# DRVLED.net
KiCad netlist of a schematic drawn in Altium Designer
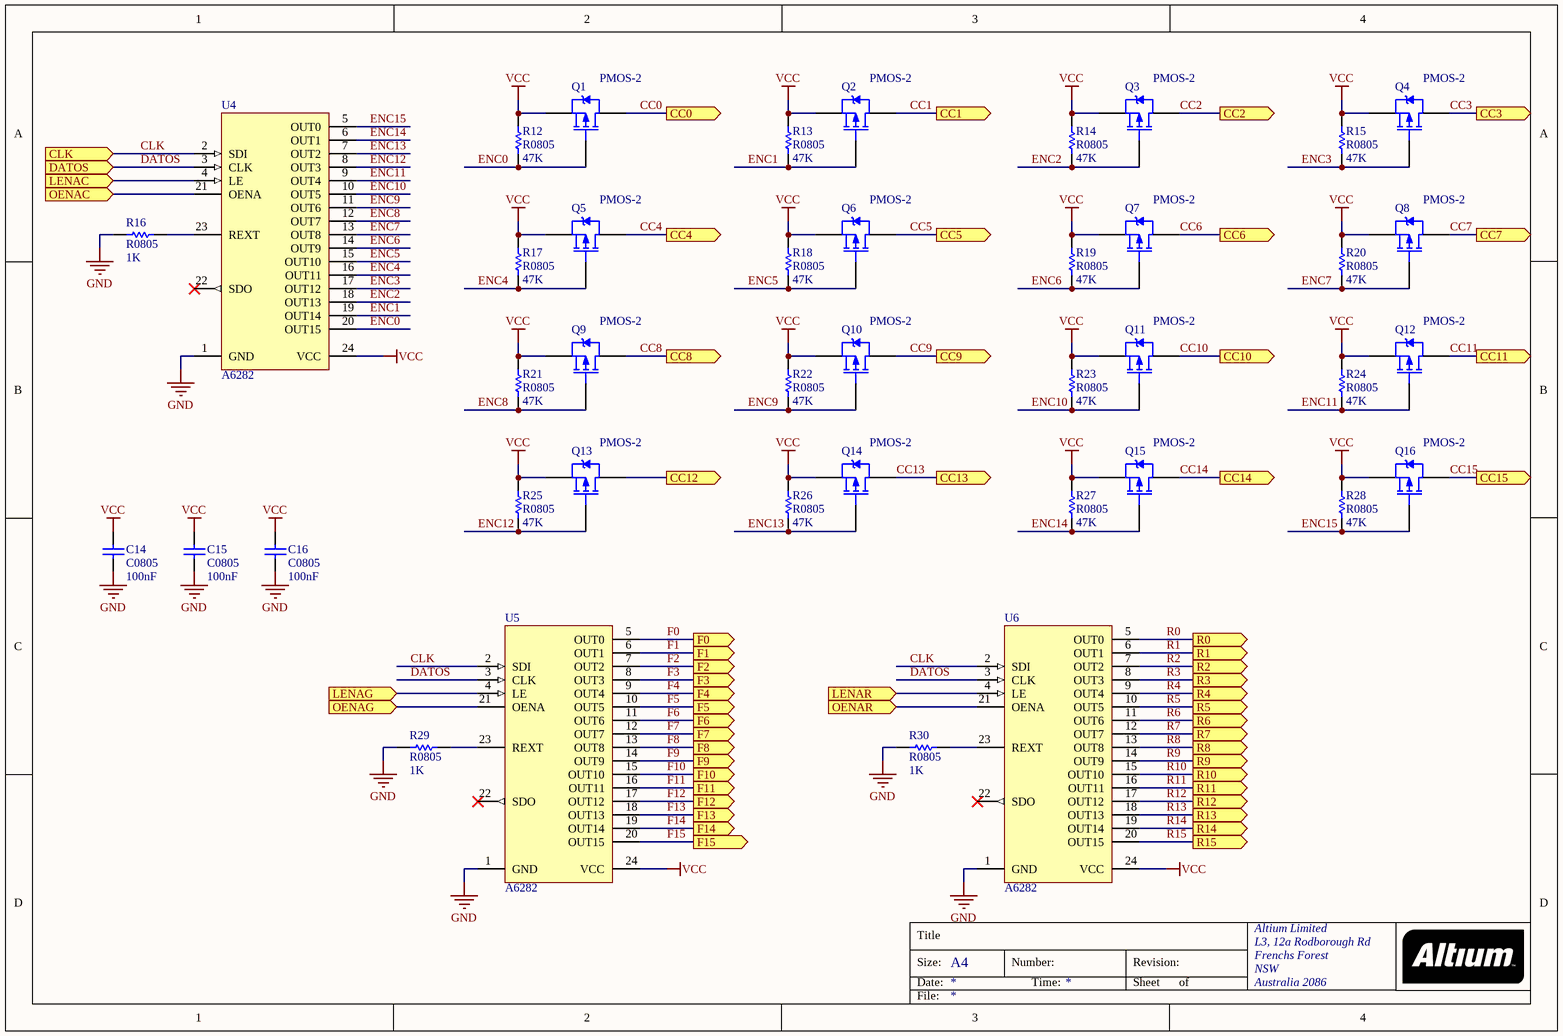
[diagram p0: DRVLED.SchDoc]

(export (version "E")
  (design (tool "Eeschema 10.0.6"))
  (components
    (comp (ref "C14")
      (value "C0805")
      (footprint "C0805C")
      (description "Cap 100nF 25V X7R")
      (fields
        (field (name "PART") "399-1170-1-ND")
        (field (name "ALTIUM_VALUE") "100nF")
        (field (name "PUBLISHER") "Altium Limited")
      )
      (libsource (lib "PROPIASchlib") (part "Cap 0805 100nF"))
    )
    (comp (ref "C15")
      (value "C0805")
      (footprint "C0805C")
      (description "Cap 100nF 25V X7R")
      (fields
        (field (name "PART") "399-1170-1-ND")
        (field (name "ALTIUM_VALUE") "100nF")
        (field (name "PUBLISHER") "Altium Limited")
      )
      (libsource (lib "PROPIASchlib") (part "Cap 0805 100nF"))
    )
    (comp (ref "C16")
      (value "C0805")
      (footprint "C0805C")
      (description "Cap 100nF 25V X7R")
      (fields
        (field (name "PART") "399-1170-1-ND")
        (field (name "ALTIUM_VALUE") "100nF")
        (field (name "PUBLISHER") "Altium Limited")
      )
      (libsource (lib "PROPIASchlib") (part "Cap 0805 100nF"))
    )
    (comp (ref "Q1")
      (value "PMOS-2")
      (footprint "SOT23MOS")
      (description "P-Channel Power MOSFET")
      (fields (field (name "PUBLISHER") "Altium Limited"))
      (libsource (lib "PROPIASchlib") (part "PMOS-2"))
    )
    (comp (ref "Q2")
      (value "PMOS-2")
      (footprint "SOT23MOS")
      (description "P-Channel Power MOSFET")
      (fields (field (name "PUBLISHER") "Altium Limited"))
      (libsource (lib "PROPIASchlib") (part "PMOS-2"))
    )
    (comp (ref "Q3")
      (value "PMOS-2")
      (footprint "SOT23MOS")
      (description "P-Channel Power MOSFET")
      (fields (field (name "PUBLISHER") "Altium Limited"))
      (libsource (lib "PROPIASchlib") (part "PMOS-2"))
    )
    (comp (ref "Q4")
      (value "PMOS-2")
      (footprint "SOT23MOS")
      (description "P-Channel Power MOSFET")
      (fields (field (name "PUBLISHER") "Altium Limited"))
      (libsource (lib "PROPIASchlib") (part "PMOS-2"))
    )
    (comp (ref "Q5")
      (value "PMOS-2")
      (footprint "SOT23MOS")
      (description "P-Channel Power MOSFET")
      (fields (field (name "PUBLISHER") "Altium Limited"))
      (libsource (lib "PROPIASchlib") (part "PMOS-2"))
    )
    (comp (ref "Q6")
      (value "PMOS-2")
      (footprint "SOT23MOS")
      (description "P-Channel Power MOSFET")
      (fields (field (name "PUBLISHER") "Altium Limited"))
      (libsource (lib "PROPIASchlib") (part "PMOS-2"))
    )
    (comp (ref "Q7")
      (value "PMOS-2")
      (footprint "SOT23MOS")
      (description "P-Channel Power MOSFET")
      (fields (field (name "PUBLISHER") "Altium Limited"))
      (libsource (lib "PROPIASchlib") (part "PMOS-2"))
    )
    (comp (ref "Q8")
      (value "PMOS-2")
      (footprint "SOT23MOS")
      (description "P-Channel Power MOSFET")
      (fields (field (name "PUBLISHER") "Altium Limited"))
      (libsource (lib "PROPIASchlib") (part "PMOS-2"))
    )
    (comp (ref "Q9")
      (value "PMOS-2")
      (footprint "SOT23MOS")
      (description "P-Channel Power MOSFET")
      (fields (field (name "PUBLISHER") "Altium Limited"))
      (libsource (lib "PROPIASchlib") (part "PMOS-2"))
    )
    (comp (ref "Q10")
      (value "PMOS-2")
      (footprint "SOT23MOS")
      (description "P-Channel Power MOSFET")
      (fields (field (name "PUBLISHER") "Altium Limited"))
      (libsource (lib "PROPIASchlib") (part "PMOS-2"))
    )
    (comp (ref "Q11")
      (value "PMOS-2")
      (footprint "SOT23MOS")
      (description "P-Channel Power MOSFET")
      (fields (field (name "PUBLISHER") "Altium Limited"))
      (libsource (lib "PROPIASchlib") (part "PMOS-2"))
    )
    (comp (ref "Q12")
      (value "PMOS-2")
      (footprint "SOT23MOS")
      (description "P-Channel Power MOSFET")
      (fields (field (name "PUBLISHER") "Altium Limited"))
      (libsource (lib "PROPIASchlib") (part "PMOS-2"))
    )
    (comp (ref "Q13")
      (value "PMOS-2")
      (footprint "SOT23MOS")
      (description "P-Channel Power MOSFET")
      (fields (field (name "PUBLISHER") "Altium Limited"))
      (libsource (lib "PROPIASchlib") (part "PMOS-2"))
    )
    (comp (ref "Q14")
      (value "PMOS-2")
      (footprint "SOT23MOS")
      (description "P-Channel Power MOSFET")
      (fields (field (name "PUBLISHER") "Altium Limited"))
      (libsource (lib "PROPIASchlib") (part "PMOS-2"))
    )
    (comp (ref "Q15")
      (value "PMOS-2")
      (footprint "SOT23MOS")
      (description "P-Channel Power MOSFET")
      (fields (field (name "PUBLISHER") "Altium Limited"))
      (libsource (lib "PROPIASchlib") (part "PMOS-2"))
    )
    (comp (ref "Q16")
      (value "PMOS-2")
      (footprint "SOT23MOS")
      (description "P-Channel Power MOSFET")
      (fields (field (name "PUBLISHER") "Altium Limited"))
      (libsource (lib "PROPIASchlib") (part "PMOS-2"))
    )
    (comp (ref "R12")
      (value "R0805")
      (footprint "R0805")
      (description "Semiconductor Resistor")
      (fields
        (field (name "PART") "311-47KARCT-ND")
        (field (name "ALTIUM_VALUE") "47K")
        (field (name "PUBLISHER") "Altium Limited")
      )
      (libsource (lib "PROPIASchlib") (part "Res 0805 47K"))
    )
    (comp (ref "R13")
      (value "R0805")
      (footprint "R0805")
      (description "Semiconductor Resistor")
      (fields
        (field (name "PART") "311-47KARCT-ND")
        (field (name "ALTIUM_VALUE") "47K")
        (field (name "PUBLISHER") "Altium Limited")
      )
      (libsource (lib "PROPIASchlib") (part "Res 0805 47K"))
    )
    (comp (ref "R14")
      (value "R0805")
      (footprint "R0805")
      (description "Semiconductor Resistor")
      (fields
        (field (name "PART") "311-47KARCT-ND")
        (field (name "ALTIUM_VALUE") "47K")
        (field (name "PUBLISHER") "Altium Limited")
      )
      (libsource (lib "PROPIASchlib") (part "Res 0805 47K"))
    )
    (comp (ref "R15")
      (value "R0805")
      (footprint "R0805")
      (description "Semiconductor Resistor")
      (fields
        (field (name "PART") "311-47KARCT-ND")
        (field (name "ALTIUM_VALUE") "47K")
        (field (name "PUBLISHER") "Altium Limited")
      )
      (libsource (lib "PROPIASchlib") (part "Res 0805 47K"))
    )
    (comp (ref "R16")
      (value "R0805")
      (footprint "R0805")
      (description "Semiconductor Resistor")
      (fields
        (field (name "PART") "311-1.0KARCT-ND")
        (field (name "ALTIUM_VALUE") "1K")
        (field (name "PUBLISHER") "Altium Limited")
      )
      (libsource (lib "PROPIASchlib") (part "Res 0805 1K"))
    )
    (comp (ref "R17")
      (value "R0805")
      (footprint "R0805")
      (description "Semiconductor Resistor")
      (fields
        (field (name "PART") "311-47KARCT-ND")
        (field (name "ALTIUM_VALUE") "47K")
        (field (name "PUBLISHER") "Altium Limited")
      )
      (libsource (lib "PROPIASchlib") (part "Res 0805 47K"))
    )
    (comp (ref "R18")
      (value "R0805")
      (footprint "R0805")
      (description "Semiconductor Resistor")
      (fields
        (field (name "PART") "311-47KARCT-ND")
        (field (name "ALTIUM_VALUE") "47K")
        (field (name "PUBLISHER") "Altium Limited")
      )
      (libsource (lib "PROPIASchlib") (part "Res 0805 47K"))
    )
    (comp (ref "R19")
      (value "R0805")
      (footprint "R0805")
      (description "Semiconductor Resistor")
      (fields
        (field (name "PART") "311-47KARCT-ND")
        (field (name "ALTIUM_VALUE") "47K")
        (field (name "PUBLISHER") "Altium Limited")
      )
      (libsource (lib "PROPIASchlib") (part "Res 0805 47K"))
    )
    (comp (ref "R20")
      (value "R0805")
      (footprint "R0805")
      (description "Semiconductor Resistor")
      (fields
        (field (name "PART") "311-47KARCT-ND")
        (field (name "ALTIUM_VALUE") "47K")
        (field (name "PUBLISHER") "Altium Limited")
      )
      (libsource (lib "PROPIASchlib") (part "Res 0805 47K"))
    )
    (comp (ref "R21")
      (value "R0805")
      (footprint "R0805")
      (description "Semiconductor Resistor")
      (fields
        (field (name "PART") "311-47KARCT-ND")
        (field (name "ALTIUM_VALUE") "47K")
        (field (name "PUBLISHER") "Altium Limited")
      )
      (libsource (lib "PROPIASchlib") (part "Res 0805 47K"))
    )
    (comp (ref "R22")
      (value "R0805")
      (footprint "R0805")
      (description "Semiconductor Resistor")
      (fields
        (field (name "PART") "311-47KARCT-ND")
        (field (name "ALTIUM_VALUE") "47K")
        (field (name "PUBLISHER") "Altium Limited")
      )
      (libsource (lib "PROPIASchlib") (part "Res 0805 47K"))
    )
    (comp (ref "R23")
      (value "R0805")
      (footprint "R0805")
      (description "Semiconductor Resistor")
      (fields
        (field (name "PART") "311-47KARCT-ND")
        (field (name "ALTIUM_VALUE") "47K")
        (field (name "PUBLISHER") "Altium Limited")
      )
      (libsource (lib "PROPIASchlib") (part "Res 0805 47K"))
    )
    (comp (ref "R24")
      (value "R0805")
      (footprint "R0805")
      (description "Semiconductor Resistor")
      (fields
        (field (name "PART") "311-47KARCT-ND")
        (field (name "ALTIUM_VALUE") "47K")
        (field (name "PUBLISHER") "Altium Limited")
      )
      (libsource (lib "PROPIASchlib") (part "Res 0805 47K"))
    )
    (comp (ref "R25")
      (value "R0805")
      (footprint "R0805")
      (description "Semiconductor Resistor")
      (fields
        (field (name "PART") "311-47KARCT-ND")
        (field (name "ALTIUM_VALUE") "47K")
        (field (name "PUBLISHER") "Altium Limited")
      )
      (libsource (lib "PROPIASchlib") (part "Res 0805 47K"))
    )
    (comp (ref "R26")
      (value "R0805")
      (footprint "R0805")
      (description "Semiconductor Resistor")
      (fields
        (field (name "PART") "311-47KARCT-ND")
        (field (name "ALTIUM_VALUE") "47K")
        (field (name "PUBLISHER") "Altium Limited")
      )
      (libsource (lib "PROPIASchlib") (part "Res 0805 47K"))
    )
    (comp (ref "R27")
      (value "R0805")
      (footprint "R0805")
      (description "Semiconductor Resistor")
      (fields
        (field (name "PART") "311-47KARCT-ND")
        (field (name "ALTIUM_VALUE") "47K")
        (field (name "PUBLISHER") "Altium Limited")
      )
      (libsource (lib "PROPIASchlib") (part "Res 0805 47K"))
    )
    (comp (ref "R28")
      (value "R0805")
      (footprint "R0805")
      (description "Semiconductor Resistor")
      (fields
        (field (name "PART") "311-47KARCT-ND")
        (field (name "ALTIUM_VALUE") "47K")
        (field (name "PUBLISHER") "Altium Limited")
      )
      (libsource (lib "PROPIASchlib") (part "Res 0805 47K"))
    )
    (comp (ref "R29")
      (value "R0805")
      (footprint "R0805")
      (description "Semiconductor Resistor")
      (fields
        (field (name "PART") "311-1.0KARCT-ND")
        (field (name "ALTIUM_VALUE") "1K")
        (field (name "PUBLISHER") "Altium Limited")
      )
      (libsource (lib "PROPIASchlib") (part "Res 0805 1K"))
    )
    (comp (ref "R30")
      (value "R0805")
      (footprint "R0805")
      (description "Semiconductor Resistor")
      (fields
        (field (name "PART") "311-1.0KARCT-ND")
        (field (name "ALTIUM_VALUE") "1K")
        (field (name "PUBLISHER") "Altium Limited")
      )
      (libsource (lib "PROPIASchlib") (part "Res 0805 1K"))
    )
    (comp (ref "U4")
      (value "A6282")
      (footprint "SOP24")
      (description "16 Bit Current Constant Driver")
      (fields (field (name "MANUFACTURER") "Allegro") (field (name "PUBLISHER") "Fernando Vasquez"))
      (libsource (lib "PROPIASchlib") (part "A6282"))
    )
    (comp (ref "U5")
      (value "A6282")
      (footprint "SOP24")
      (description "16 Bit Current Constant Driver")
      (fields (field (name "MANUFACTURER") "Allegro") (field (name "PUBLISHER") "Fernando Vasquez"))
      (libsource (lib "PROPIASchlib") (part "A6282"))
    )
    (comp (ref "U6")
      (value "A6282")
      (footprint "SOP24")
      (description "16 Bit Current Constant Driver")
      (fields (field (name "MANUFACTURER") "Allegro") (field (name "PUBLISHER") "Fernando Vasquez"))
      (libsource (lib "PROPIASchlib") (part "A6282"))
    )
  )
  (nets
    (net (code "1") (name "/CC0") (class "Default")
      (node (ref "Q1") (pin "2") (pinfunction "D_2") (pintype "passive"))
    )
    (net (code "2") (name "/CC1") (class "Default")
      (node (ref "Q2") (pin "2") (pinfunction "D_2") (pintype "passive"))
    )
    (net (code "3") (name "/CC2") (class "Default")
      (node (ref "Q3") (pin "2") (pinfunction "D_2") (pintype "passive"))
    )
    (net (code "4") (name "/CC3") (class "Default")
      (node (ref "Q4") (pin "2") (pinfunction "D_2") (pintype "passive"))
    )
    (net (code "5") (name "/CC4") (class "Default")
      (node (ref "Q5") (pin "2") (pinfunction "D_2") (pintype "passive"))
    )
    (net (code "6") (name "/CC5") (class "Default")
      (node (ref "Q6") (pin "2") (pinfunction "D_2") (pintype "passive"))
    )
    (net (code "7") (name "/CC6") (class "Default")
      (node (ref "Q7") (pin "2") (pinfunction "D_2") (pintype "passive"))
    )
    (net (code "8") (name "/CC7") (class "Default")
      (node (ref "Q8") (pin "2") (pinfunction "D_2") (pintype "passive"))
    )
    (net (code "9") (name "/CC8") (class "Default")
      (node (ref "Q9") (pin "2") (pinfunction "D_2") (pintype "passive"))
    )
    (net (code "10") (name "/CC9") (class "Default")
      (node (ref "Q10") (pin "2") (pinfunction "D_2") (pintype "passive"))
    )
    (net (code "11") (name "/CC10") (class "Default")
      (node (ref "Q11") (pin "2") (pinfunction "D_2") (pintype "passive"))
    )
    (net (code "12") (name "/CC11") (class "Default")
      (node (ref "Q12") (pin "2") (pinfunction "D_2") (pintype "passive"))
    )
    (net (code "13") (name "/CC12") (class "Default")
      (node (ref "Q13") (pin "2") (pinfunction "D_2") (pintype "passive"))
    )
    (net (code "14") (name "/CC13") (class "Default")
      (node (ref "Q14") (pin "2") (pinfunction "D_2") (pintype "passive"))
    )
    (net (code "15") (name "/CC14") (class "Default")
      (node (ref "Q15") (pin "2") (pinfunction "D_2") (pintype "passive"))
    )
    (net (code "16") (name "/CC15") (class "Default")
      (node (ref "Q16") (pin "2") (pinfunction "D_2") (pintype "passive"))
    )
    (net (code "17") (name "/CLK") (class "Default")
      (node (ref "U4") (pin "2") (pinfunction "SDI_2") (pintype "input"))
      (node (ref "U5") (pin "2") (pinfunction "SDI_2") (pintype "input"))
      (node (ref "U6") (pin "2") (pinfunction "SDI_2") (pintype "input"))
    )
    (net (code "18") (name "/DATOS") (class "Default")
      (node (ref "U4") (pin "3") (pinfunction "CLK_3") (pintype "input"))
      (node (ref "U5") (pin "3") (pinfunction "CLK_3") (pintype "input"))
      (node (ref "U6") (pin "3") (pinfunction "CLK_3") (pintype "input"))
    )
    (net (code "19") (name "/ENC0") (class "Default")
      (node (ref "Q1") (pin "1") (pinfunction "G_1") (pintype "passive"))
      (node (ref "R12") (pin "1") (pinfunction "1_1") (pintype "passive"))
      (node (ref "U4") (pin "20") (pinfunction "OUT15_20") (pintype "open_collector"))
    )
    (net (code "20") (name "/ENC1") (class "Default")
      (node (ref "Q2") (pin "1") (pinfunction "G_1") (pintype "passive"))
      (node (ref "R13") (pin "1") (pinfunction "1_1") (pintype "passive"))
      (node (ref "U4") (pin "19") (pinfunction "OUT14_19") (pintype "open_collector"))
    )
    (net (code "21") (name "/ENC2") (class "Default")
      (node (ref "Q3") (pin "1") (pinfunction "G_1") (pintype "passive"))
      (node (ref "R14") (pin "1") (pinfunction "1_1") (pintype "passive"))
      (node (ref "U4") (pin "18") (pinfunction "OUT13_18") (pintype "open_collector"))
    )
    (net (code "22") (name "/ENC3") (class "Default")
      (node (ref "Q4") (pin "1") (pinfunction "G_1") (pintype "passive"))
      (node (ref "R15") (pin "1") (pinfunction "1_1") (pintype "passive"))
      (node (ref "U4") (pin "17") (pinfunction "OUT12_17") (pintype "open_collector"))
    )
    (net (code "23") (name "/ENC4") (class "Default")
      (node (ref "Q5") (pin "1") (pinfunction "G_1") (pintype "passive"))
      (node (ref "R17") (pin "1") (pinfunction "1_1") (pintype "passive"))
      (node (ref "U4") (pin "16") (pinfunction "OUT11_16") (pintype "open_collector"))
    )
    (net (code "24") (name "/ENC5") (class "Default")
      (node (ref "Q6") (pin "1") (pinfunction "G_1") (pintype "passive"))
      (node (ref "R18") (pin "1") (pinfunction "1_1") (pintype "passive"))
      (node (ref "U4") (pin "15") (pinfunction "OUT10_15") (pintype "open_collector"))
    )
    (net (code "25") (name "/ENC6") (class "Default")
      (node (ref "Q7") (pin "1") (pinfunction "G_1") (pintype "passive"))
      (node (ref "R19") (pin "1") (pinfunction "1_1") (pintype "passive"))
      (node (ref "U4") (pin "14") (pinfunction "OUT9_14") (pintype "open_collector"))
    )
    (net (code "26") (name "/ENC7") (class "Default")
      (node (ref "Q8") (pin "1") (pinfunction "G_1") (pintype "passive"))
      (node (ref "R20") (pin "1") (pinfunction "1_1") (pintype "passive"))
      (node (ref "U4") (pin "13") (pinfunction "OUT8_13") (pintype "open_collector"))
    )
    (net (code "27") (name "/ENC8") (class "Default")
      (node (ref "Q9") (pin "1") (pinfunction "G_1") (pintype "passive"))
      (node (ref "R21") (pin "1") (pinfunction "1_1") (pintype "passive"))
      (node (ref "U4") (pin "12") (pinfunction "OUT7_12") (pintype "open_collector"))
    )
    (net (code "28") (name "/ENC9") (class "Default")
      (node (ref "Q10") (pin "1") (pinfunction "G_1") (pintype "passive"))
      (node (ref "R22") (pin "1") (pinfunction "1_1") (pintype "passive"))
      (node (ref "U4") (pin "11") (pinfunction "OUT6_11") (pintype "open_collector"))
    )
    (net (code "29") (name "/ENC10") (class "Default")
      (node (ref "Q11") (pin "1") (pinfunction "G_1") (pintype "passive"))
      (node (ref "R23") (pin "1") (pinfunction "1_1") (pintype "passive"))
      (node (ref "U4") (pin "10") (pinfunction "OUT5_10") (pintype "open_collector"))
    )
    (net (code "30") (name "/ENC11") (class "Default")
      (node (ref "Q12") (pin "1") (pinfunction "G_1") (pintype "passive"))
      (node (ref "R24") (pin "1") (pinfunction "1_1") (pintype "passive"))
      (node (ref "U4") (pin "9") (pinfunction "OUT4_9") (pintype "open_collector"))
    )
    (net (code "31") (name "/ENC12") (class "Default")
      (node (ref "Q13") (pin "1") (pinfunction "G_1") (pintype "passive"))
      (node (ref "R25") (pin "1") (pinfunction "1_1") (pintype "passive"))
      (node (ref "U4") (pin "8") (pinfunction "OUT3_8") (pintype "open_collector"))
    )
    (net (code "32") (name "/ENC13") (class "Default")
      (node (ref "Q14") (pin "1") (pinfunction "G_1") (pintype "passive"))
      (node (ref "R26") (pin "1") (pinfunction "1_1") (pintype "passive"))
      (node (ref "U4") (pin "7") (pinfunction "OUT2_7") (pintype "open_collector"))
    )
    (net (code "33") (name "/ENC14") (class "Default")
      (node (ref "Q15") (pin "1") (pinfunction "G_1") (pintype "passive"))
      (node (ref "R27") (pin "1") (pinfunction "1_1") (pintype "passive"))
      (node (ref "U4") (pin "6") (pinfunction "OUT1_6") (pintype "open_collector"))
    )
    (net (code "34") (name "/ENC15") (class "Default")
      (node (ref "Q16") (pin "1") (pinfunction "G_1") (pintype "passive"))
      (node (ref "R28") (pin "1") (pinfunction "1_1") (pintype "passive"))
      (node (ref "U4") (pin "5") (pinfunction "OUT0_5") (pintype "open_collector"))
    )
    (net (code "35") (name "/F0") (class "Default")
      (node (ref "U5") (pin "5") (pinfunction "OUT0_5") (pintype "open_collector"))
    )
    (net (code "36") (name "/F1") (class "Default")
      (node (ref "U5") (pin "6") (pinfunction "OUT1_6") (pintype "open_collector"))
    )
    (net (code "37") (name "/F2") (class "Default")
      (node (ref "U5") (pin "7") (pinfunction "OUT2_7") (pintype "open_collector"))
    )
    (net (code "38") (name "/F3") (class "Default")
      (node (ref "U5") (pin "8") (pinfunction "OUT3_8") (pintype "open_collector"))
    )
    (net (code "39") (name "/F4") (class "Default")
      (node (ref "U5") (pin "9") (pinfunction "OUT4_9") (pintype "open_collector"))
    )
    (net (code "40") (name "/F5") (class "Default")
      (node (ref "U5") (pin "10") (pinfunction "OUT5_10") (pintype "open_collector"))
    )
    (net (code "41") (name "/F6") (class "Default")
      (node (ref "U5") (pin "11") (pinfunction "OUT6_11") (pintype "open_collector"))
    )
    (net (code "42") (name "/F7") (class "Default")
      (node (ref "U5") (pin "12") (pinfunction "OUT7_12") (pintype "open_collector"))
    )
    (net (code "43") (name "/F8") (class "Default")
      (node (ref "U5") (pin "13") (pinfunction "OUT8_13") (pintype "open_collector"))
    )
    (net (code "44") (name "/F9") (class "Default")
      (node (ref "U5") (pin "14") (pinfunction "OUT9_14") (pintype "open_collector"))
    )
    (net (code "45") (name "/F10") (class "Default")
      (node (ref "U5") (pin "15") (pinfunction "OUT10_15") (pintype "open_collector"))
    )
    (net (code "46") (name "/F11") (class "Default")
      (node (ref "U5") (pin "16") (pinfunction "OUT11_16") (pintype "open_collector"))
    )
    (net (code "47") (name "/F12") (class "Default")
      (node (ref "U5") (pin "17") (pinfunction "OUT12_17") (pintype "open_collector"))
    )
    (net (code "48") (name "/F13") (class "Default")
      (node (ref "U5") (pin "18") (pinfunction "OUT13_18") (pintype "open_collector"))
    )
    (net (code "49") (name "/F14") (class "Default")
      (node (ref "U5") (pin "19") (pinfunction "OUT14_19") (pintype "open_collector"))
    )
    (net (code "50") (name "/F15") (class "Default")
      (node (ref "U5") (pin "20") (pinfunction "OUT15_20") (pintype "open_collector"))
    )
    (net (code "51") (name "/LENAC") (class "Default")
      (node (ref "U4") (pin "4") (pinfunction "LE_4") (pintype "input"))
    )
    (net (code "52") (name "/LENAG") (class "Default")
      (node (ref "U5") (pin "4") (pinfunction "LE_4") (pintype "input"))
    )
    (net (code "53") (name "/LENAR") (class "Default")
      (node (ref "U6") (pin "4") (pinfunction "LE_4") (pintype "input"))
    )
    (net (code "54") (name "/OENAC") (class "Default")
      (node (ref "U4") (pin "21") (pinfunction "OENA_21") (pintype "passive"))
    )
    (net (code "55") (name "/OENAG") (class "Default")
      (node (ref "U5") (pin "21") (pinfunction "OENA_21") (pintype "passive"))
    )
    (net (code "56") (name "/OENAR") (class "Default")
      (node (ref "U6") (pin "21") (pinfunction "OENA_21") (pintype "passive"))
    )
    (net (code "57") (name "/R0") (class "Default")
      (node (ref "U6") (pin "5") (pinfunction "OUT0_5") (pintype "open_collector"))
    )
    (net (code "58") (name "/R1") (class "Default")
      (node (ref "U6") (pin "6") (pinfunction "OUT1_6") (pintype "open_collector"))
    )
    (net (code "59") (name "/R2") (class "Default")
      (node (ref "U6") (pin "7") (pinfunction "OUT2_7") (pintype "open_collector"))
    )
    (net (code "60") (name "/R3") (class "Default")
      (node (ref "U6") (pin "8") (pinfunction "OUT3_8") (pintype "open_collector"))
    )
    (net (code "61") (name "/R4") (class "Default")
      (node (ref "U6") (pin "9") (pinfunction "OUT4_9") (pintype "open_collector"))
    )
    (net (code "62") (name "/R5") (class "Default")
      (node (ref "U6") (pin "10") (pinfunction "OUT5_10") (pintype "open_collector"))
    )
    (net (code "63") (name "/R6") (class "Default")
      (node (ref "U6") (pin "11") (pinfunction "OUT6_11") (pintype "open_collector"))
    )
    (net (code "64") (name "/R7") (class "Default")
      (node (ref "U6") (pin "12") (pinfunction "OUT7_12") (pintype "open_collector"))
    )
    (net (code "65") (name "/R8") (class "Default")
      (node (ref "U6") (pin "13") (pinfunction "OUT8_13") (pintype "open_collector"))
    )
    (net (code "66") (name "/R9") (class "Default")
      (node (ref "U6") (pin "14") (pinfunction "OUT9_14") (pintype "open_collector"))
    )
    (net (code "67") (name "/R10") (class "Default")
      (node (ref "U6") (pin "15") (pinfunction "OUT10_15") (pintype "open_collector"))
    )
    (net (code "68") (name "/R11") (class "Default")
      (node (ref "U6") (pin "16") (pinfunction "OUT11_16") (pintype "open_collector"))
    )
    (net (code "69") (name "/R12") (class "Default")
      (node (ref "U6") (pin "17") (pinfunction "OUT12_17") (pintype "open_collector"))
    )
    (net (code "70") (name "/R13") (class "Default")
      (node (ref "U6") (pin "18") (pinfunction "OUT13_18") (pintype "open_collector"))
    )
    (net (code "71") (name "/R14") (class "Default")
      (node (ref "U6") (pin "19") (pinfunction "OUT14_19") (pintype "open_collector"))
    )
    (net (code "72") (name "/R15") (class "Default")
      (node (ref "U6") (pin "20") (pinfunction "OUT15_20") (pintype "open_collector"))
    )
    (net (code "73") (name "GND") (class "Default")
      (node (ref "C14") (pin "1") (pinfunction "1_1") (pintype "passive"))
      (node (ref "C15") (pin "1") (pinfunction "1_1") (pintype "passive"))
      (node (ref "C16") (pin "1") (pinfunction "1_1") (pintype "passive"))
      (node (ref "R16") (pin "1") (pinfunction "1_1") (pintype "passive"))
      (node (ref "R29") (pin "1") (pinfunction "1_1") (pintype "passive"))
      (node (ref "R30") (pin "1") (pinfunction "1_1") (pintype "passive"))
      (node (ref "U4") (pin "1") (pinfunction "GND_1") (pintype "power_in"))
      (node (ref "U5") (pin "1") (pinfunction "GND_1") (pintype "power_in"))
      (node (ref "U6") (pin "1") (pinfunction "GND_1") (pintype "power_in"))
    )
    (net (code "74") (name "Net-(U4-REXT)") (class "Default")
      (node (ref "R16") (pin "2") (pinfunction "2_2") (pintype "passive"))
      (node (ref "U4") (pin "23") (pinfunction "REXT_23") (pintype "passive"))
    )
    (net (code "75") (name "Net-(U5-REXT)") (class "Default")
      (node (ref "R29") (pin "2") (pinfunction "2_2") (pintype "passive"))
      (node (ref "U5") (pin "23") (pinfunction "REXT_23") (pintype "passive"))
    )
    (net (code "76") (name "Net-(U6-REXT)") (class "Default")
      (node (ref "R30") (pin "2") (pinfunction "2_2") (pintype "passive"))
      (node (ref "U6") (pin "23") (pinfunction "REXT_23") (pintype "passive"))
    )
    (net (code "77") (name "VCC") (class "Default")
      (node (ref "C14") (pin "2") (pinfunction "2_2") (pintype "passive"))
      (node (ref "C15") (pin "2") (pinfunction "2_2") (pintype "passive"))
      (node (ref "C16") (pin "2") (pinfunction "2_2") (pintype "passive"))
      (node (ref "Q1") (pin "3") (pinfunction "S_3") (pintype "passive"))
      (node (ref "Q10") (pin "3") (pinfunction "S_3") (pintype "passive"))
      (node (ref "Q11") (pin "3") (pinfunction "S_3") (pintype "passive"))
      (node (ref "Q12") (pin "3") (pinfunction "S_3") (pintype "passive"))
      (node (ref "Q13") (pin "3") (pinfunction "S_3") (pintype "passive"))
      (node (ref "Q14") (pin "3") (pinfunction "S_3") (pintype "passive"))
      (node (ref "Q15") (pin "3") (pinfunction "S_3") (pintype "passive"))
      (node (ref "Q16") (pin "3") (pinfunction "S_3") (pintype "passive"))
      (node (ref "Q2") (pin "3") (pinfunction "S_3") (pintype "passive"))
      (node (ref "Q3") (pin "3") (pinfunction "S_3") (pintype "passive"))
      (node (ref "Q4") (pin "3") (pinfunction "S_3") (pintype "passive"))
      (node (ref "Q5") (pin "3") (pinfunction "S_3") (pintype "passive"))
      (node (ref "Q6") (pin "3") (pinfunction "S_3") (pintype "passive"))
      (node (ref "Q7") (pin "3") (pinfunction "S_3") (pintype "passive"))
      (node (ref "Q8") (pin "3") (pinfunction "S_3") (pintype "passive"))
      (node (ref "Q9") (pin "3") (pinfunction "S_3") (pintype "passive"))
      (node (ref "R12") (pin "2") (pinfunction "2_2") (pintype "passive"))
      (node (ref "R13") (pin "2") (pinfunction "2_2") (pintype "passive"))
      (node (ref "R14") (pin "2") (pinfunction "2_2") (pintype "passive"))
      (node (ref "R15") (pin "2") (pinfunction "2_2") (pintype "passive"))
      (node (ref "R17") (pin "2") (pinfunction "2_2") (pintype "passive"))
      (node (ref "R18") (pin "2") (pinfunction "2_2") (pintype "passive"))
      (node (ref "R19") (pin "2") (pinfunction "2_2") (pintype "passive"))
      (node (ref "R20") (pin "2") (pinfunction "2_2") (pintype "passive"))
      (node (ref "R21") (pin "2") (pinfunction "2_2") (pintype "passive"))
      (node (ref "R22") (pin "2") (pinfunction "2_2") (pintype "passive"))
      (node (ref "R23") (pin "2") (pinfunction "2_2") (pintype "passive"))
      (node (ref "R24") (pin "2") (pinfunction "2_2") (pintype "passive"))
      (node (ref "R25") (pin "2") (pinfunction "2_2") (pintype "passive"))
      (node (ref "R26") (pin "2") (pinfunction "2_2") (pintype "passive"))
      (node (ref "R27") (pin "2") (pinfunction "2_2") (pintype "passive"))
      (node (ref "R28") (pin "2") (pinfunction "2_2") (pintype "passive"))
      (node (ref "U4") (pin "24") (pinfunction "VCC_24") (pintype "power_in"))
      (node (ref "U5") (pin "24") (pinfunction "VCC_24") (pintype "power_in"))
      (node (ref "U6") (pin "24") (pinfunction "VCC_24") (pintype "power_in"))
    )
    (net (code "78") (name "unconnected-(U4-SDO-Pad22)") (class "Default")
      (node (ref "U4") (pin "22") (pinfunction "SDO_22") (pintype "output+no_connect"))
    )
    (net (code "79") (name "unconnected-(U5-SDO-Pad22)") (class "Default")
      (node (ref "U5") (pin "22") (pinfunction "SDO_22") (pintype "output+no_connect"))
    )
    (net (code "80") (name "unconnected-(U6-SDO-Pad22)") (class "Default")
      (node (ref "U6") (pin "22") (pinfunction "SDO_22") (pintype "output+no_connect"))
    )
  )
)
